# USBasp.net
KiCad netlist of a schematic drawn in EAGLE
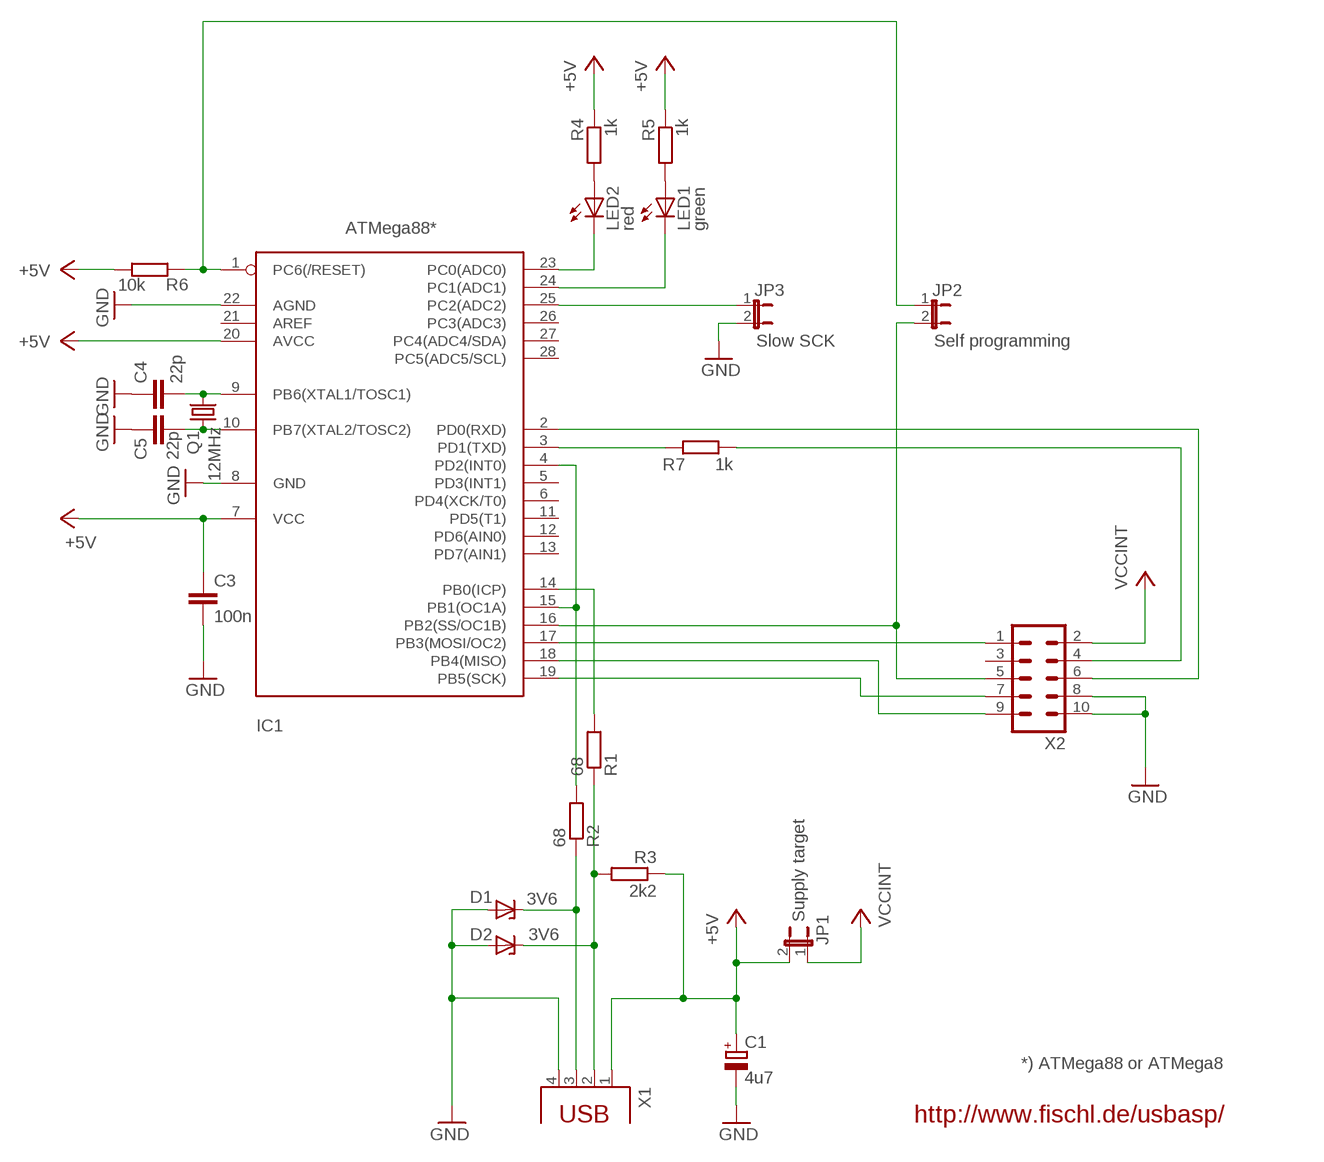
[diagram p0: schematic, sheet 1]

(export (version "E")
  (design (tool "Eeschema 10.0.6"))
  (components
    (comp (ref "C1")
      (value "4u7")
      (footprint "eagle-import:E2,5-5")
      (libsource (lib "eagle-import") (part "CPOL-EUE2.5-5"))
    )
    (comp (ref "C3")
      (value "100n")
      (footprint "eagle-import:C025-024X044")
      (libsource (lib "eagle-import") (part "C-EU025-024X044"))
    )
    (comp (ref "C4")
      (value "22p")
      (footprint "eagle-import:C025-024X044")
      (libsource (lib "eagle-import") (part "C-EU025-024X044"))
    )
    (comp (ref "C5")
      (value "22p")
      (footprint "eagle-import:C025-024X044")
      (libsource (lib "eagle-import") (part "C-EU025-024X044"))
    )
    (comp (ref "D1")
      (value "3V6")
      (footprint "eagle-import:DO34Z7")
      (libsource (lib "eagle-import") (part "ZENER-DIODEDO34-7"))
    )
    (comp (ref "D2")
      (value "3V6")
      (footprint "eagle-import:DO34Z7")
      (libsource (lib "eagle-import") (part "ZENER-DIODEDO34-7"))
    )
    (comp (ref "IC1")
      (value "ATMega88*")
      (footprint "eagle-import:DIL28-3")
      (libsource (lib "eagle-import") (part "MEGA8-P"))
    )
    (comp (ref "JP1")
      (value "Supply target")
      (footprint "eagle-import:JP1")
      (libsource (lib "eagle-import") (part "JP1E"))
    )
    (comp (ref "JP2")
      (value "Self programming")
      (footprint "eagle-import:JP1")
      (libsource (lib "eagle-import") (part "JP1E"))
    )
    (comp (ref "JP3")
      (value "Slow SCK")
      (footprint "eagle-import:JP1")
      (libsource (lib "eagle-import") (part "JP1E"))
    )
    (comp (ref "LED1")
      (value "green")
      (footprint "eagle-import:LED3MM")
      (libsource (lib "eagle-import") (part "LED3MM"))
    )
    (comp (ref "LED2")
      (value "red")
      (footprint "eagle-import:LED3MM")
      (libsource (lib "eagle-import") (part "LED3MM"))
    )
    (comp (ref "Q1")
      (value "12MHz")
      (footprint "eagle-import:HC49_S")
      (libsource (lib "eagle-import") (part "CRYTALHC49S"))
    )
    (comp (ref "R1")
      (value "68")
      (footprint "eagle-import:0207_10")
      (libsource (lib "eagle-import") (part "R-EU_0207/10"))
    )
    (comp (ref "R2")
      (value "68")
      (footprint "eagle-import:0207_10")
      (libsource (lib "eagle-import") (part "R-EU_0207/10"))
    )
    (comp (ref "R3")
      (value "2k2")
      (footprint "eagle-import:0207_10")
      (libsource (lib "eagle-import") (part "R-EU_0207/10"))
    )
    (comp (ref "R4")
      (value "1k")
      (footprint "eagle-import:0207_10")
      (libsource (lib "eagle-import") (part "R-EU_0207/10"))
    )
    (comp (ref "R5")
      (value "1k")
      (footprint "eagle-import:0207_10")
      (libsource (lib "eagle-import") (part "R-EU_0207/10"))
    )
    (comp (ref "R6")
      (value "10k")
      (footprint "eagle-import:0207_10")
      (libsource (lib "eagle-import") (part "R-EU_0207/10"))
    )
    (comp (ref "R7")
      (value "1k")
      (footprint "eagle-import:0207_10")
      (libsource (lib "eagle-import") (part "R-EU_0207/10"))
    )
    (comp (ref "X1")
      (value "PN61729")
      (footprint "eagle-import:PN61729")
      (libsource (lib "eagle-import") (part "PN61729"))
    )
    (comp (ref "X2")
      (value "ML10L")
      (footprint "eagle-import:ML10L")
      (libsource (lib "eagle-import") (part "ML10L"))
    )
  )
  (nets
    (net (code "1") (name "+5V") (class "Default")
      (node (ref "C1") (pin "+") (pinfunction "+_+") (pintype "passive"))
      (node (ref "C3") (pin "1") (pinfunction "1_1") (pintype "passive"))
      (node (ref "IC1") (pin "20") (pinfunction "AVCC_20") (pintype "bidirectional"))
      (node (ref "IC1") (pin "7") (pinfunction "VCC_7") (pintype "bidirectional"))
      (node (ref "JP1") (pin "2") (pinfunction "2_2") (pintype "passive"))
      (node (ref "R3") (pin "1") (pinfunction "1_1") (pintype "passive"))
      (node (ref "R4") (pin "1") (pinfunction "1_1") (pintype "passive"))
      (node (ref "R5") (pin "1") (pinfunction "1_1") (pintype "passive"))
      (node (ref "R6") (pin "1") (pinfunction "1_1") (pintype "passive"))
      (node (ref "X1") (pin "1") (pinfunction "1_1") (pintype "bidirectional"))
    )
    (net (code "2") (name "GND") (class "Default")
      (node (ref "C1") (pin "-") (pinfunction "-_-") (pintype "passive"))
      (node (ref "C3") (pin "2") (pinfunction "2_2") (pintype "passive"))
      (node (ref "C4") (pin "1") (pinfunction "1_1") (pintype "passive"))
      (node (ref "C5") (pin "1") (pinfunction "1_1") (pintype "passive"))
      (node (ref "D1") (pin "A") (pinfunction "A_A") (pintype "passive"))
      (node (ref "D2") (pin "A") (pinfunction "A_A") (pintype "passive"))
      (node (ref "IC1") (pin "22") (pinfunction "AGND_22") (pintype "bidirectional"))
      (node (ref "IC1") (pin "8") (pinfunction "GND_8") (pintype "bidirectional"))
      (node (ref "JP3") (pin "2") (pinfunction "2_2") (pintype "passive"))
      (node (ref "X1") (pin "4") (pinfunction "4_4") (pintype "bidirectional"))
      (node (ref "X2") (pin "10") (pinfunction "10_10") (pintype "passive"))
      (node (ref "X2") (pin "8") (pinfunction "8_8") (pintype "passive"))
    )
    (net (code "3") (name "Net-(D1-PadC)") (class "Default")
      (node (ref "D1") (pin "C") (pinfunction "C_C") (pintype "passive"))
      (node (ref "R2") (pin "1") (pinfunction "1_1") (pintype "passive"))
      (node (ref "X1") (pin "3") (pinfunction "3_3") (pintype "bidirectional"))
    )
    (net (code "4") (name "Net-(D2-PadC)") (class "Default")
      (node (ref "D2") (pin "C") (pinfunction "C_C") (pintype "passive"))
      (node (ref "R1") (pin "1") (pinfunction "1_1") (pintype "passive"))
      (node (ref "R3") (pin "2") (pinfunction "2_2") (pintype "passive"))
      (node (ref "X1") (pin "2") (pinfunction "2_2") (pintype "bidirectional"))
    )
    (net (code "5") (name "Net-(IC1-PB0(ICP))") (class "Default")
      (node (ref "IC1") (pin "14") (pinfunction "PB0(ICP)_14") (pintype "bidirectional"))
      (node (ref "R1") (pin "2") (pinfunction "2_2") (pintype "passive"))
    )
    (net (code "6") (name "Net-(IC1-PB1(OC1A))") (class "Default")
      (node (ref "IC1") (pin "15") (pinfunction "PB1(OC1A)_15") (pintype "bidirectional"))
      (node (ref "IC1") (pin "4") (pinfunction "PD2(INT0)_4") (pintype "bidirectional"))
      (node (ref "R2") (pin "2") (pinfunction "2_2") (pintype "passive"))
    )
    (net (code "7") (name "Net-(IC1-PB2(SS{slash}OC1B))") (class "Default")
      (node (ref "IC1") (pin "16") (pinfunction "PB2(SS/OC1B)_16") (pintype "bidirectional"))
      (node (ref "JP2") (pin "2") (pinfunction "2_2") (pintype "passive"))
      (node (ref "X2") (pin "5") (pinfunction "5_5") (pintype "passive"))
    )
    (net (code "8") (name "Net-(IC1-PB3(MOSI{slash}OC2))") (class "Default")
      (node (ref "IC1") (pin "17") (pinfunction "PB3(MOSI/OC2)_17") (pintype "bidirectional"))
      (node (ref "X2") (pin "1") (pinfunction "1_1") (pintype "passive"))
    )
    (net (code "9") (name "Net-(IC1-PB4(MISO))") (class "Default")
      (node (ref "IC1") (pin "18") (pinfunction "PB4(MISO)_18") (pintype "bidirectional"))
      (node (ref "X2") (pin "9") (pinfunction "9_9") (pintype "passive"))
    )
    (net (code "10") (name "Net-(IC1-PB5(SCK))") (class "Default")
      (node (ref "IC1") (pin "19") (pinfunction "PB5(SCK)_19") (pintype "bidirectional"))
      (node (ref "X2") (pin "7") (pinfunction "7_7") (pintype "passive"))
    )
    (net (code "11") (name "Net-(IC1-PB6(XTAL1{slash}TOSC1))") (class "Default")
      (node (ref "C4") (pin "2") (pinfunction "2_2") (pintype "passive"))
      (node (ref "IC1") (pin "9") (pinfunction "PB6(XTAL1/TOSC1)_9") (pintype "bidirectional"))
      (node (ref "Q1") (pin "2") (pinfunction "2_2") (pintype "passive"))
    )
    (net (code "12") (name "Net-(IC1-PB7(XTAL2{slash}TOSC2))") (class "Default")
      (node (ref "C5") (pin "2") (pinfunction "2_2") (pintype "passive"))
      (node (ref "IC1") (pin "10") (pinfunction "PB7(XTAL2/TOSC2)_10") (pintype "bidirectional"))
      (node (ref "Q1") (pin "1") (pinfunction "1_1") (pintype "passive"))
    )
    (net (code "13") (name "Net-(IC1-PC0(ADC0))") (class "Default")
      (node (ref "IC1") (pin "23") (pinfunction "PC0(ADC0)_23") (pintype "bidirectional"))
      (node (ref "LED2") (pin "K") (pinfunction "C_K") (pintype "passive"))
    )
    (net (code "14") (name "Net-(IC1-PC1(ADC1))") (class "Default")
      (node (ref "IC1") (pin "24") (pinfunction "PC1(ADC1)_24") (pintype "bidirectional"))
      (node (ref "LED1") (pin "K") (pinfunction "C_K") (pintype "passive"))
    )
    (net (code "15") (name "Net-(IC1-PC2(ADC2))") (class "Default")
      (node (ref "IC1") (pin "25") (pinfunction "PC2(ADC2)_25") (pintype "bidirectional"))
      (node (ref "JP3") (pin "1") (pinfunction "1_1") (pintype "passive"))
    )
    (net (code "16") (name "Net-(IC1-PC6({slash}RESET))") (class "Default")
      (node (ref "IC1") (pin "1") (pinfunction "PC6(/RESET)_1") (pintype "bidirectional"))
      (node (ref "JP2") (pin "1") (pinfunction "1_1") (pintype "passive"))
      (node (ref "R6") (pin "2") (pinfunction "2_2") (pintype "passive"))
    )
    (net (code "17") (name "Net-(IC1-PD0(RXD))") (class "Default")
      (node (ref "IC1") (pin "2") (pinfunction "PD0(RXD)_2") (pintype "bidirectional"))
      (node (ref "X2") (pin "6") (pinfunction "6_6") (pintype "passive"))
    )
    (net (code "18") (name "Net-(IC1-PD1(TXD))") (class "Default")
      (node (ref "IC1") (pin "3") (pinfunction "PD1(TXD)_3") (pintype "bidirectional"))
      (node (ref "R7") (pin "2") (pinfunction "2_2") (pintype "passive"))
    )
    (net (code "19") (name "Net-(LED1-PadA)") (class "Default")
      (node (ref "LED1") (pin "A") (pinfunction "A_A") (pintype "passive"))
      (node (ref "R5") (pin "2") (pinfunction "2_2") (pintype "passive"))
    )
    (net (code "20") (name "Net-(LED2-PadA)") (class "Default")
      (node (ref "LED2") (pin "A") (pinfunction "A_A") (pintype "passive"))
      (node (ref "R4") (pin "2") (pinfunction "2_2") (pintype "passive"))
    )
    (net (code "21") (name "Net-(R7-Pad1)") (class "Default")
      (node (ref "R7") (pin "1") (pinfunction "1_1") (pintype "passive"))
      (node (ref "X2") (pin "4") (pinfunction "4_4") (pintype "passive"))
    )
    (net (code "22") (name "VCCINT") (class "Default")
      (node (ref "JP1") (pin "1") (pinfunction "1_1") (pintype "passive"))
      (node (ref "X2") (pin "2") (pinfunction "2_2") (pintype "passive"))
    )
    (net (code "23") (name "unconnected-(IC1-AREF-Pad21)") (class "Default")
      (node (ref "IC1") (pin "21") (pinfunction "AREF_21") (pintype "bidirectional"))
    )
    (net (code "24") (name "unconnected-(IC1-PC3(ADC3)-Pad26)") (class "Default")
      (node (ref "IC1") (pin "26") (pinfunction "PC3(ADC3)_26") (pintype "bidirectional"))
    )
    (net (code "25") (name "unconnected-(IC1-PC4(ADC4{slash}SDA)-Pad27)") (class "Default")
      (node (ref "IC1") (pin "27") (pinfunction "PC4(ADC4/SDA)_27") (pintype "bidirectional"))
    )
    (net (code "26") (name "unconnected-(IC1-PC5(ADC5{slash}SCL)-Pad28)") (class "Default")
      (node (ref "IC1") (pin "28") (pinfunction "PC5(ADC5/SCL)_28") (pintype "bidirectional"))
    )
    (net (code "27") (name "unconnected-(IC1-PD3(INT1)-Pad5)") (class "Default")
      (node (ref "IC1") (pin "5") (pinfunction "PD3(INT1)_5") (pintype "bidirectional"))
    )
    (net (code "28") (name "unconnected-(IC1-PD4(XCK{slash}T0)-Pad6)") (class "Default")
      (node (ref "IC1") (pin "6") (pinfunction "PD4(XCK/T0)_6") (pintype "bidirectional"))
    )
    (net (code "29") (name "unconnected-(IC1-PD5(T1)-Pad11)") (class "Default")
      (node (ref "IC1") (pin "11") (pinfunction "PD5(T1)_11") (pintype "bidirectional"))
    )
    (net (code "30") (name "unconnected-(IC1-PD6(AIN0)-Pad12)") (class "Default")
      (node (ref "IC1") (pin "12") (pinfunction "PD6(AIN0)_12") (pintype "bidirectional"))
    )
    (net (code "31") (name "unconnected-(IC1-PD7(AIN1)-Pad13)") (class "Default")
      (node (ref "IC1") (pin "13") (pinfunction "PD7(AIN1)_13") (pintype "bidirectional"))
    )
    (net (code "32") (name "unconnected-(X2-Pad3)") (class "Default")
      (node (ref "X2") (pin "3") (pinfunction "3_3") (pintype "passive"))
    )
  )
)
